# Esquema.net
KiCad netlist of a schematic drawn in EAGLE
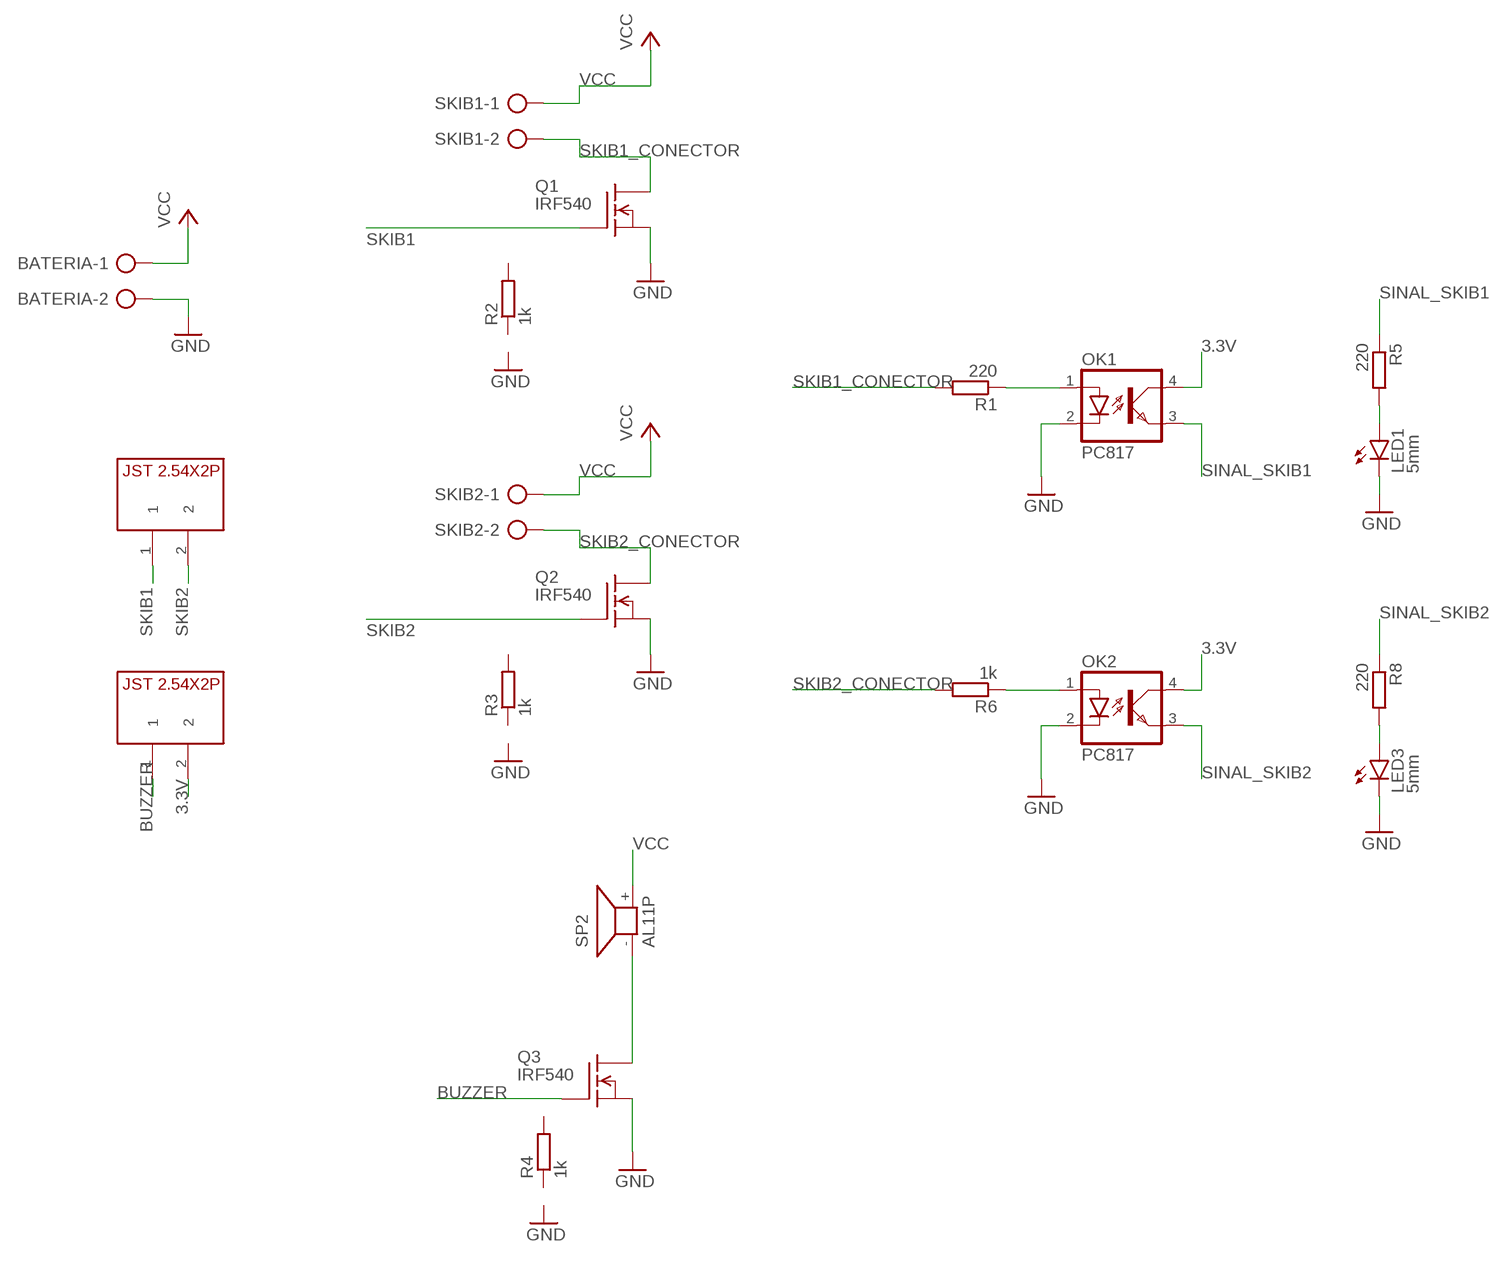
[diagram p0: schematic, sheet 1]

(export (version "E")
  (design (tool "Eeschema 10.0.6"))
  (components
    (comp (ref "BATERIA")
      (value "AK500/2-H")
      (footprint "eagle-import:AK500_2-H")
      (libsource (lib "eagle-import") (part "AK500/2-H"))
    )
    (comp (ref "LED1")
      (value "5mm")
      (footprint "eagle-import:LED5MM")
      (libsource (lib "eagle-import") (part "LED5MM"))
    )
    (comp (ref "LED3")
      (value "5mm")
      (footprint "eagle-import:LED5MM")
      (libsource (lib "eagle-import") (part "LED5MM"))
    )
    (comp (ref "OK1")
      (value "PC817")
      (footprint "eagle-import:DIL04")
      (fields (field (name "MPN") "PC817X4J000F"))
      (libsource (lib "eagle-import") (part "PC817"))
    )
    (comp (ref "OK2")
      (value "PC817")
      (footprint "eagle-import:DIL04")
      (fields (field (name "MPN") "PC817X4J000F"))
      (libsource (lib "eagle-import") (part "PC817"))
    )
    (comp (ref "Q1")
      (value "IRF540")
      (footprint "eagle-import:TO220")
      (libsource (lib "eagle-import") (part "IRF540"))
    )
    (comp (ref "Q2")
      (value "IRF540")
      (footprint "eagle-import:TO220")
      (libsource (lib "eagle-import") (part "IRF540"))
    )
    (comp (ref "Q3")
      (value "IRF540")
      (footprint "eagle-import:TO220")
      (libsource (lib "eagle-import") (part "IRF540"))
    )
    (comp (ref "R1")
      (value "220")
      (footprint "eagle-import:0207_10")
      (libsource (lib "eagle-import") (part "R-EU_0207/10"))
    )
    (comp (ref "R2")
      (value "1k")
      (footprint "eagle-import:0207_10")
      (libsource (lib "eagle-import") (part "R-EU_0207/10"))
    )
    (comp (ref "R3")
      (value "1k")
      (footprint "eagle-import:0207_10")
      (libsource (lib "eagle-import") (part "R-EU_0207/10"))
    )
    (comp (ref "R4")
      (value "1k")
      (footprint "eagle-import:0207_10")
      (libsource (lib "eagle-import") (part "R-EU_0207/10"))
    )
    (comp (ref "R5")
      (value "220")
      (footprint "eagle-import:0207_10")
      (libsource (lib "eagle-import") (part "R-EU_0207/10"))
    )
    (comp (ref "R6")
      (value "1k")
      (footprint "eagle-import:0207_10")
      (libsource (lib "eagle-import") (part "R-EU_0207/10"))
    )
    (comp (ref "R8")
      (value "220")
      (footprint "eagle-import:0207_10")
      (libsource (lib "eagle-import") (part "R-EU_0207/10"))
    )
    (comp (ref "SKIB1")
      (value "AK500/2-H")
      (footprint "eagle-import:AK500_2-H")
      (libsource (lib "eagle-import") (part "AK500/2-H"))
    )
    (comp (ref "SKIB2")
      (value "AK500/2-H")
      (footprint "eagle-import:AK500_2-H")
      (libsource (lib "eagle-import") (part "AK500/2-H"))
    )
    (comp (ref "SP2")
      (value "AL11P")
      (footprint "eagle-import:AL11P")
      (libsource (lib "eagle-import") (part "AL11P"))
    )
    (comp (ref "U$1")
      (value "JST2.54X2P")
      (footprint "eagle-import:JST2.54X2P_FOOTPRINT")
      (libsource (lib "eagle-import") (part "JST2.54X2P"))
    )
    (comp (ref "U$2")
      (value "JST2.54X2P")
      (footprint "eagle-import:JST2.54X2P_FOOTPRINT")
      (libsource (lib "eagle-import") (part "JST2.54X2P"))
    )
  )
  (nets
    (net (code "1") (name "/3.3V") (class "Default")
      (node (ref "OK1") (pin "4") (pinfunction "COL_4") (pintype "passive"))
      (node (ref "OK2") (pin "4") (pinfunction "COL_4") (pintype "passive"))
      (node (ref "U$1") (pin "2") (pinfunction "2_2") (pintype "bidirectional"))
    )
    (net (code "2") (name "/BUZZER") (class "Default")
      (node (ref "Q3") (pin "1") (pinfunction "G_1") (pintype "passive"))
      (node (ref "U$1") (pin "1") (pinfunction "1_1") (pintype "bidirectional"))
    )
    (net (code "3") (name "/SINAL_SKIB1") (class "Default")
      (node (ref "OK1") (pin "3") (pinfunction "EMIT_3") (pintype "passive"))
      (node (ref "R5") (pin "1") (pinfunction "1_1") (pintype "passive"))
    )
    (net (code "4") (name "/SINAL_SKIB2") (class "Default")
      (node (ref "OK2") (pin "3") (pinfunction "EMIT_3") (pintype "passive"))
      (node (ref "R8") (pin "1") (pinfunction "1_1") (pintype "passive"))
    )
    (net (code "5") (name "/SKIB1") (class "Default")
      (node (ref "Q1") (pin "1") (pinfunction "G_1") (pintype "passive"))
      (node (ref "U$2") (pin "1") (pinfunction "1_1") (pintype "bidirectional"))
    )
    (net (code "6") (name "/SKIB1_CONECTOR") (class "Default")
      (node (ref "Q1") (pin "2") (pinfunction "D_2") (pintype "passive"))
      (node (ref "R1") (pin "2") (pinfunction "2_2") (pintype "passive"))
      (node (ref "SKIB1") (pin "2") (pinfunction "KL_2") (pintype "passive"))
    )
    (net (code "7") (name "/SKIB2") (class "Default")
      (node (ref "Q2") (pin "1") (pinfunction "G_1") (pintype "passive"))
      (node (ref "U$2") (pin "2") (pinfunction "2_2") (pintype "bidirectional"))
    )
    (net (code "8") (name "/SKIB2_CONECTOR") (class "Default")
      (node (ref "Q2") (pin "2") (pinfunction "D_2") (pintype "passive"))
      (node (ref "R6") (pin "2") (pinfunction "2_2") (pintype "passive"))
      (node (ref "SKIB2") (pin "2") (pinfunction "KL_2") (pintype "passive"))
    )
    (net (code "9") (name "GND") (class "Default")
      (node (ref "BATERIA") (pin "2") (pinfunction "KL_2") (pintype "passive"))
      (node (ref "LED1") (pin "K") (pinfunction "C_K") (pintype "passive"))
      (node (ref "LED3") (pin "K") (pinfunction "C_K") (pintype "passive"))
      (node (ref "OK1") (pin "2") (pinfunction "C_2") (pintype "passive"))
      (node (ref "OK2") (pin "2") (pinfunction "C_2") (pintype "passive"))
      (node (ref "Q1") (pin "3") (pinfunction "S_3") (pintype "passive"))
      (node (ref "Q2") (pin "3") (pinfunction "S_3") (pintype "passive"))
      (node (ref "Q3") (pin "3") (pinfunction "S_3") (pintype "passive"))
    )
    (net (code "10") (name "Net-(LED1-PadA)") (class "Default")
      (node (ref "LED1") (pin "A") (pinfunction "A_A") (pintype "passive"))
      (node (ref "R5") (pin "2") (pinfunction "2_2") (pintype "passive"))
    )
    (net (code "11") (name "Net-(LED3-PadA)") (class "Default")
      (node (ref "LED3") (pin "A") (pinfunction "A_A") (pintype "passive"))
      (node (ref "R8") (pin "2") (pinfunction "2_2") (pintype "passive"))
    )
    (net (code "12") (name "Net-(OK1-A)") (class "Default")
      (node (ref "OK1") (pin "1") (pinfunction "A_1") (pintype "passive"))
      (node (ref "R1") (pin "1") (pinfunction "1_1") (pintype "passive"))
    )
    (net (code "13") (name "Net-(OK2-A)") (class "Default")
      (node (ref "OK2") (pin "1") (pinfunction "A_1") (pintype "passive"))
      (node (ref "R6") (pin "1") (pinfunction "1_1") (pintype "passive"))
    )
    (net (code "14") (name "Net-(Q3-D)") (class "Default")
      (node (ref "Q3") (pin "2") (pinfunction "D_2") (pintype "passive"))
      (node (ref "SP2") (pin "-") (pinfunction "1_-") (pintype "passive"))
    )
    (net (code "15") (name "VCC") (class "Default")
      (node (ref "BATERIA") (pin "1") (pinfunction "KL_1") (pintype "passive"))
      (node (ref "SKIB1") (pin "1") (pinfunction "KL_1") (pintype "passive"))
      (node (ref "SKIB2") (pin "1") (pinfunction "KL_1") (pintype "passive"))
      (node (ref "SP2") (pin "+") (pinfunction "2_+") (pintype "passive"))
    )
    (net (code "16") (name "unconnected-(R2-Pad1)") (class "Default")
      (node (ref "R2") (pin "1") (pinfunction "1_1") (pintype "passive"))
    )
    (net (code "17") (name "unconnected-(R2-Pad2)") (class "Default")
      (node (ref "R2") (pin "2") (pinfunction "2_2") (pintype "passive"))
    )
    (net (code "18") (name "unconnected-(R3-Pad1)") (class "Default")
      (node (ref "R3") (pin "1") (pinfunction "1_1") (pintype "passive"))
    )
    (net (code "19") (name "unconnected-(R3-Pad2)") (class "Default")
      (node (ref "R3") (pin "2") (pinfunction "2_2") (pintype "passive"))
    )
    (net (code "20") (name "unconnected-(R4-Pad1)") (class "Default")
      (node (ref "R4") (pin "1") (pinfunction "1_1") (pintype "passive"))
    )
    (net (code "21") (name "unconnected-(R4-Pad2)") (class "Default")
      (node (ref "R4") (pin "2") (pinfunction "2_2") (pintype "passive"))
    )
  )
)
